# Danyboard_M0.net
KiCad netlist of a schematic drawn in EAGLE
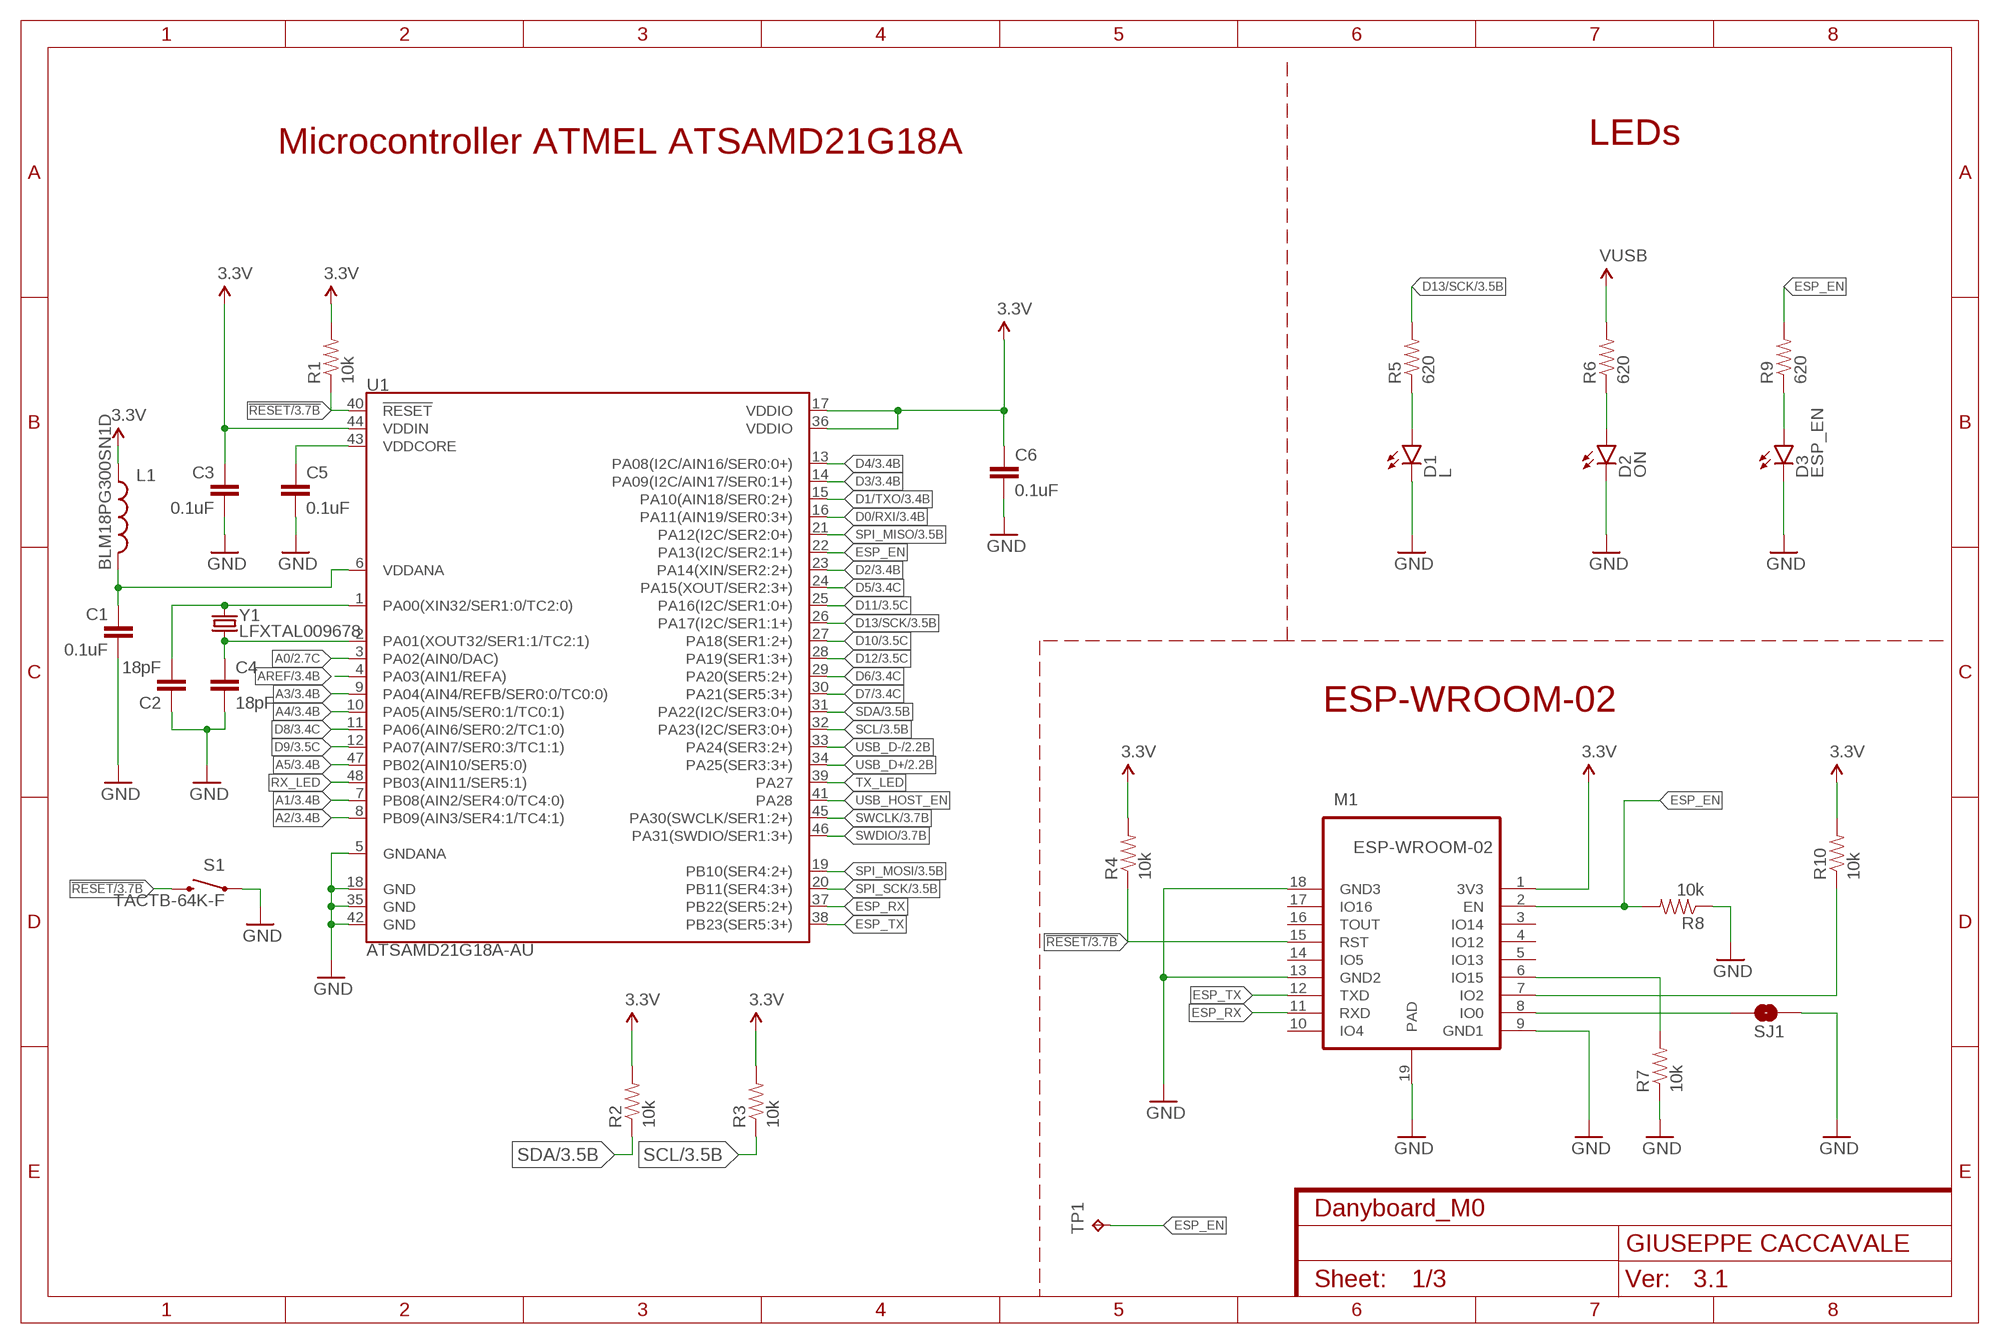
[diagram p0: schematic, sheet 1]
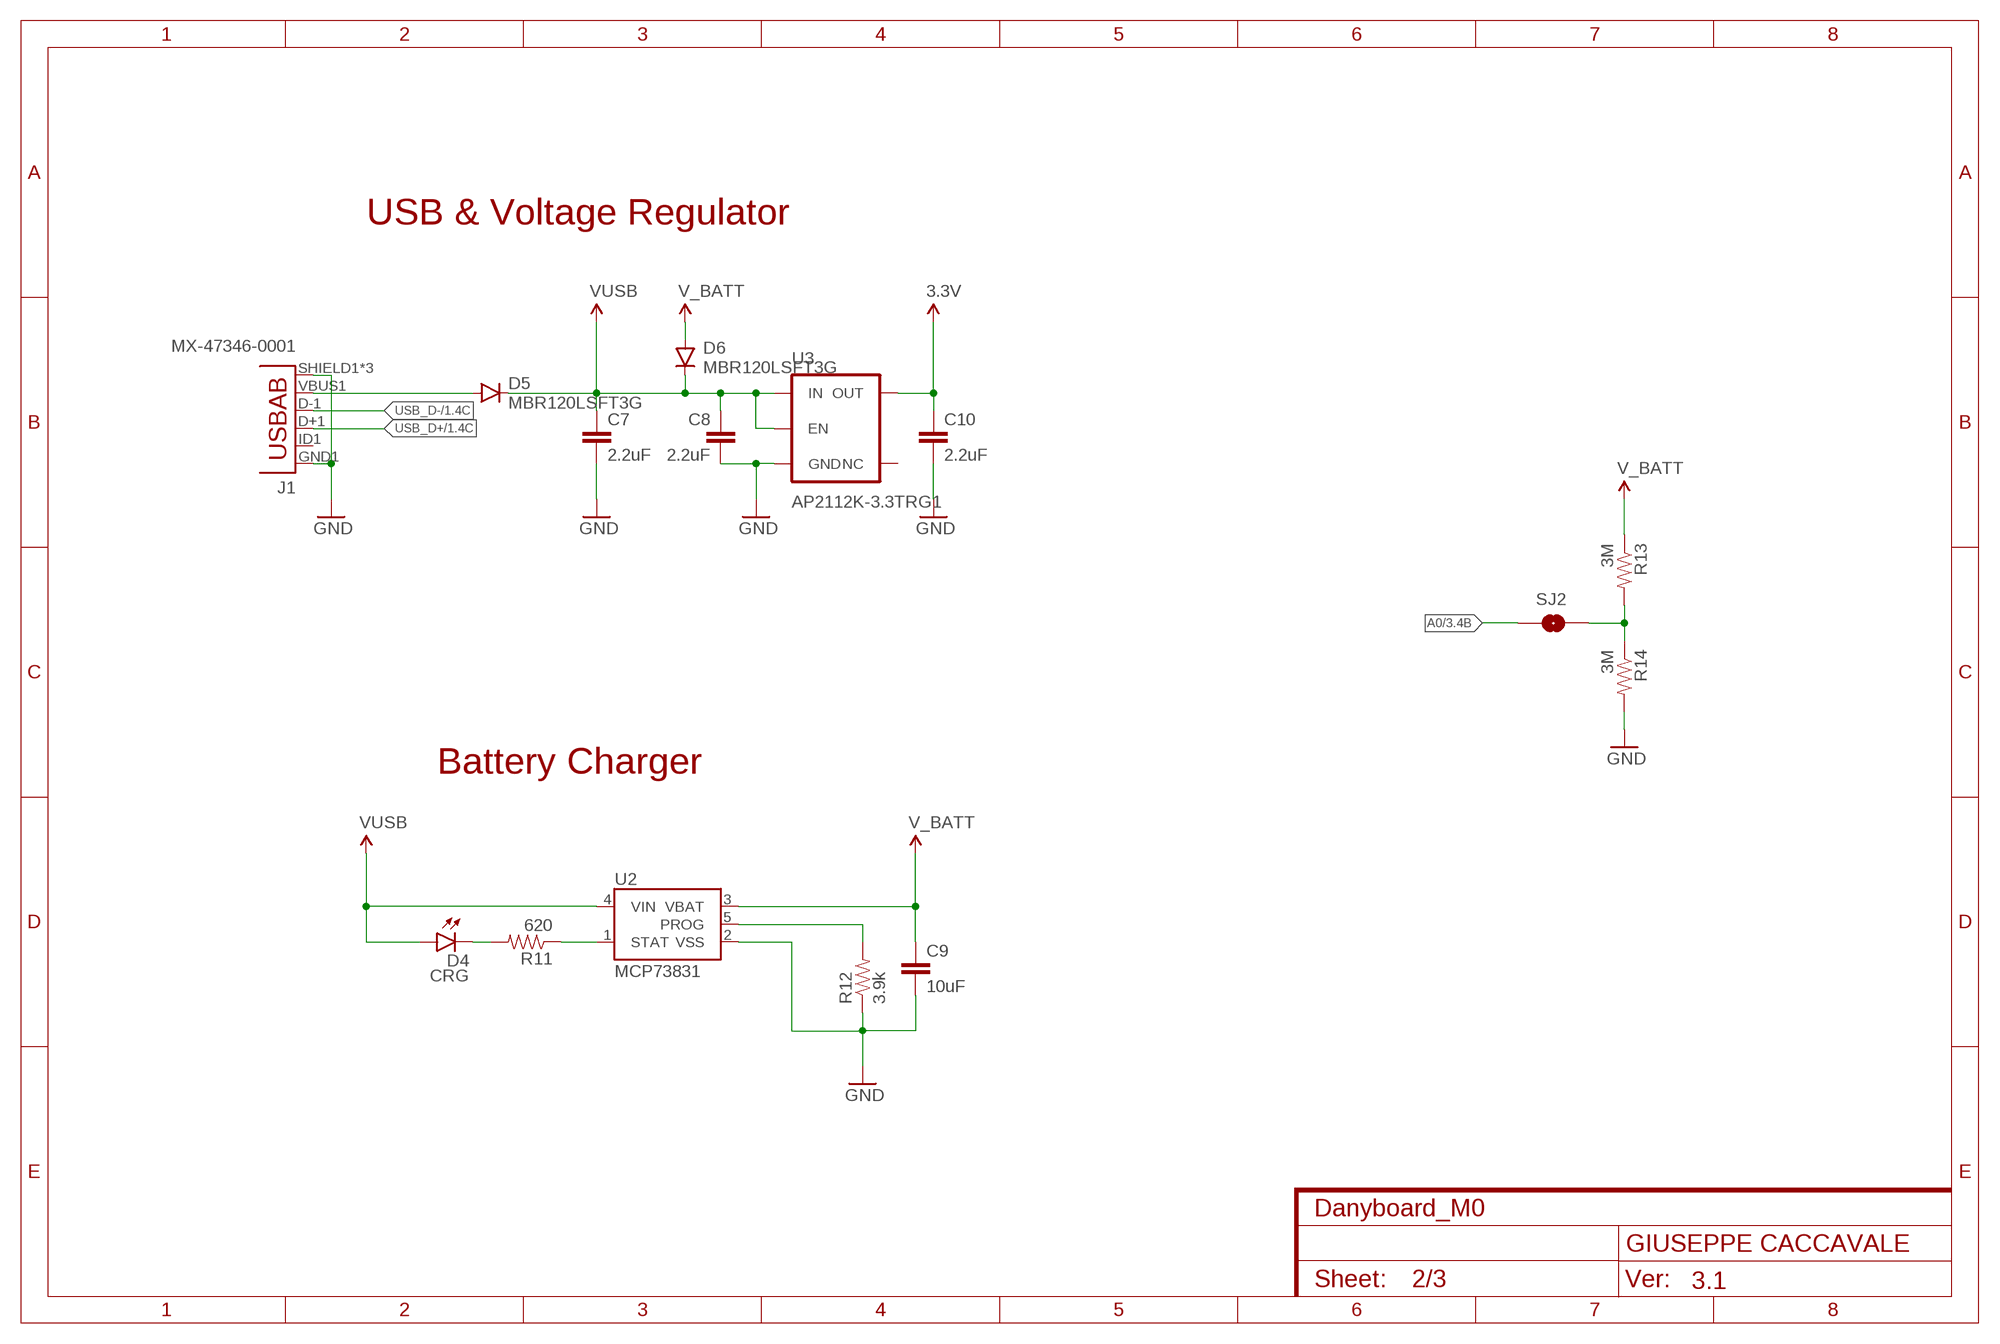
[diagram p1: schematic, sheet 2]
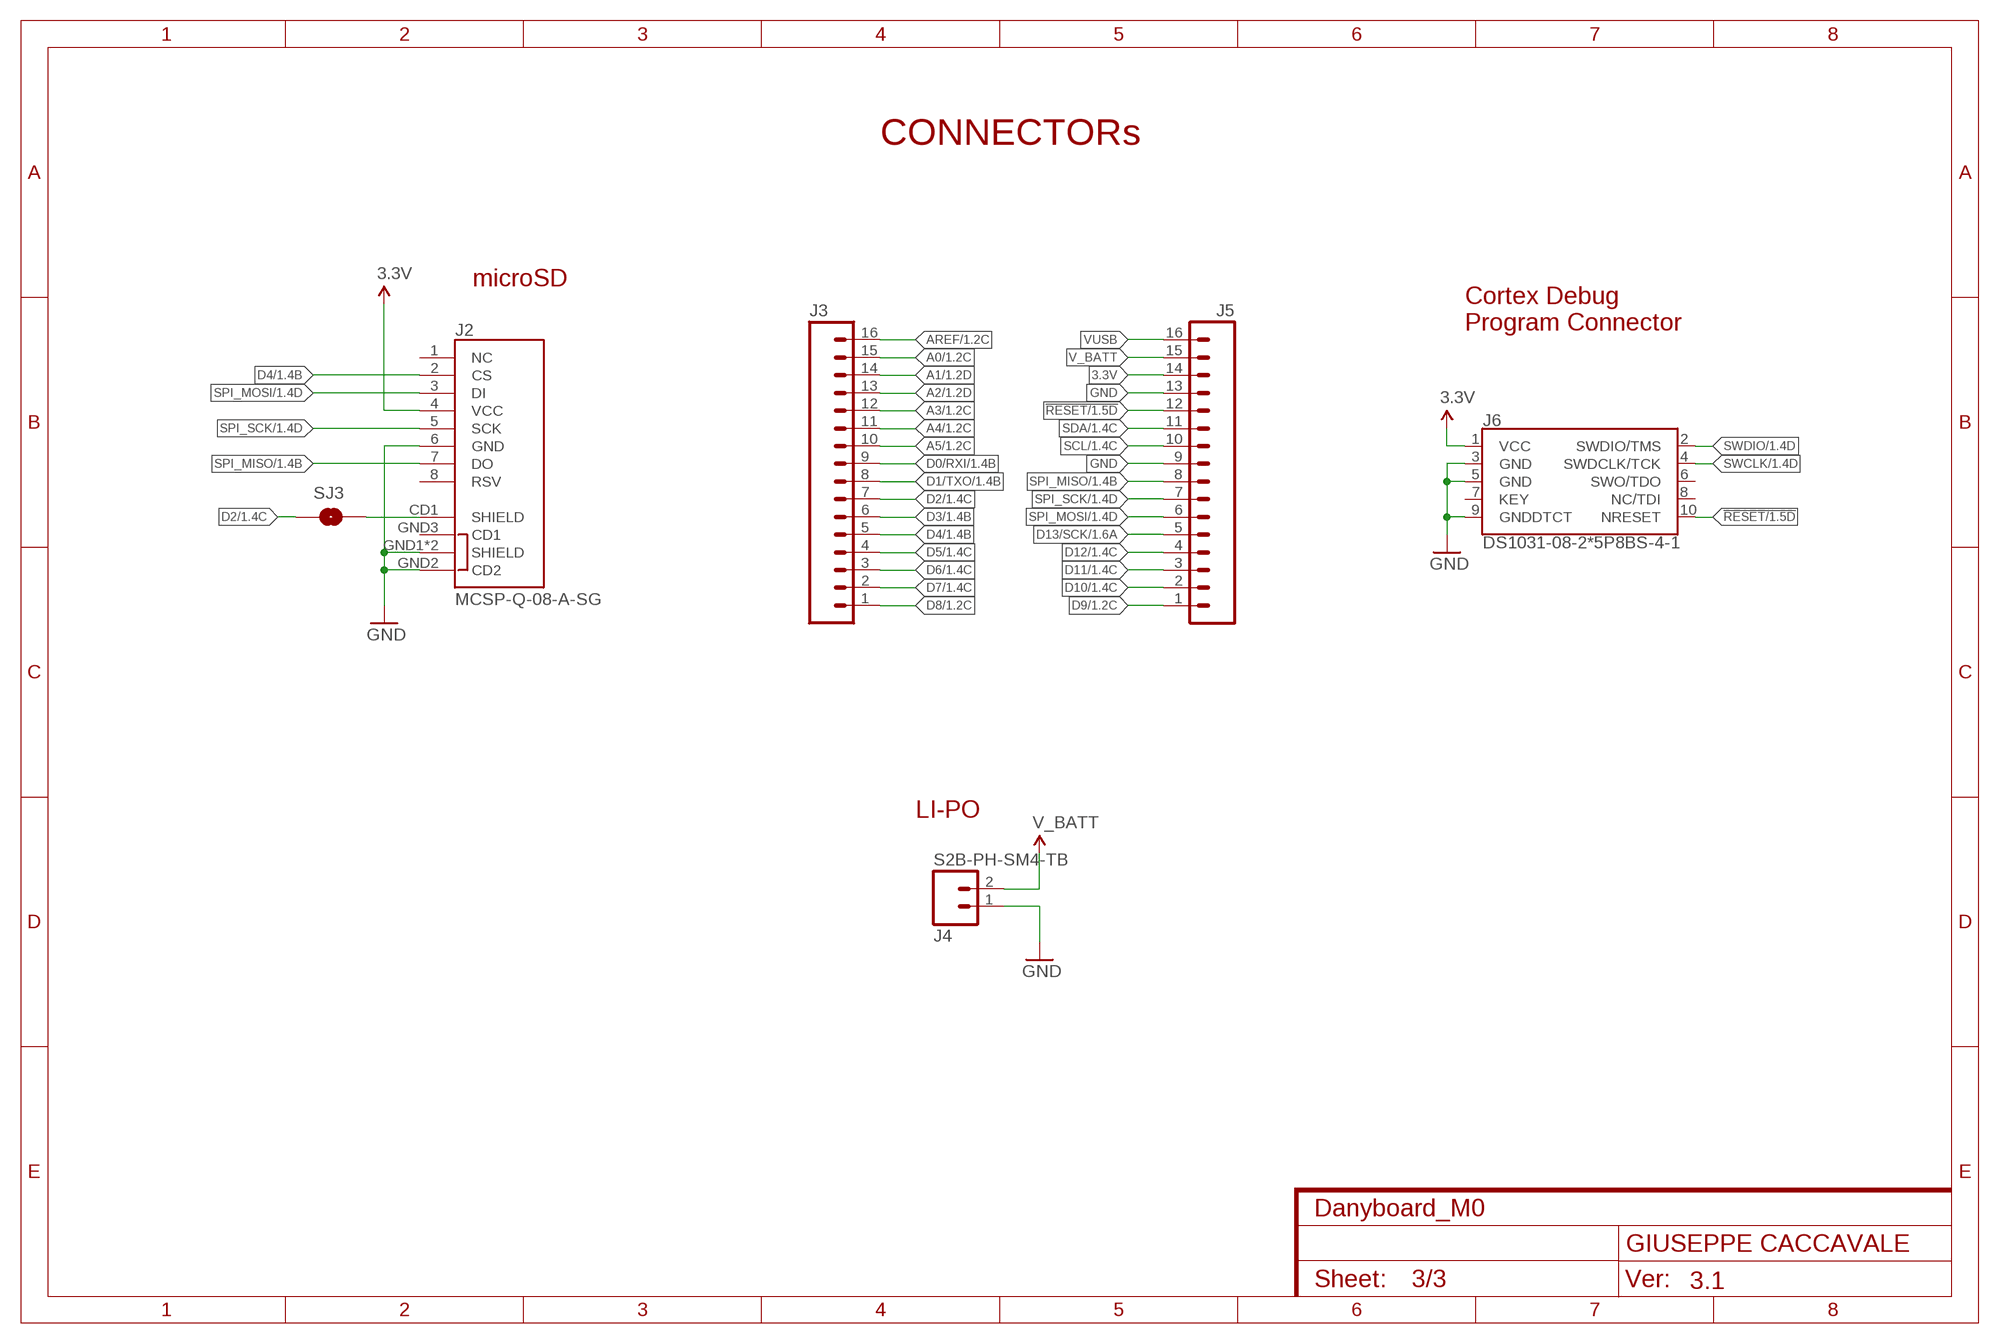
[diagram p2: schematic, sheet 3]

(export (version "E")
  (design (tool "Eeschema 10.0.6"))
  (components
    (comp (ref "C7")
      (value "2.2uF")
      (footprint "eagle-import:0603-CAP_NOSILK")
      (libsource (lib "eagle-import") (part "CAP0603-CAP_NS"))
    )
    (comp (ref "C8")
      (value "2.2uF")
      (footprint "eagle-import:0603-CAP_NOSILK")
      (libsource (lib "eagle-import") (part "CAP0603-CAP_NS"))
    )
    (comp (ref "C9")
      (value "10uF")
      (footprint "eagle-import:0603-CAP_NOSILK")
      (libsource (lib "eagle-import") (part "CAP0603-CAP_NS"))
    )
    (comp (ref "C10")
      (value "2.2uF")
      (footprint "eagle-import:0603-CAP_NOSILK")
      (libsource (lib "eagle-import") (part "CAP0603-CAP_NS"))
    )
    (comp (ref "D4")
      (value "CRG")
      (footprint "eagle-import:LED-0603")
      (libsource (lib "eagle-import") (part "LED0603"))
    )
    (comp (ref "D5")
      (value "MBR120LSFT3G")
      (footprint "eagle-import:SOD-123_NOSILK")
      (libsource (lib "eagle-import") (part "DIODESOD123_NS"))
    )
    (comp (ref "D6")
      (value "MBR120LSFT3G")
      (footprint "eagle-import:SOD-123_NOSILK")
      (libsource (lib "eagle-import") (part "DIODESOD123_NS"))
    )
    (comp (ref "J1")
      (value "MX-47346-0001")
      (footprint "eagle-import:USB-AB-MICRO-SMD_V03")
      (libsource (lib "eagle-import") (part "USB-ABCONN-11794"))
    )
    (comp (ref "R11")
      (value "620")
      (footprint "eagle-import:0603-RES_NOSILK")
      (libsource (lib "eagle-import") (part "RESISTOR0603-NS"))
    )
    (comp (ref "R12")
      (value "3.9k")
      (footprint "eagle-import:0603-RES_NOSILK")
      (libsource (lib "eagle-import") (part "RESISTOR0603-NS"))
    )
    (comp (ref "R13")
      (value "3M")
      (footprint "eagle-import:0603-RES_NOSILK")
      (libsource (lib "eagle-import") (part "RESISTOR0603-NS"))
    )
    (comp (ref "R14")
      (value "3M")
      (footprint "eagle-import:0603-RES_NOSILK")
      (libsource (lib "eagle-import") (part "RESISTOR0603-NS"))
    )
    (comp (ref "SJ2")
      (value "SOLDERJUMPERNO")
      (footprint "eagle-import:SJ_2S-NO")
      (libsource (lib "eagle-import") (part "SOLDERJUMPERNO"))
    )
    (comp (ref "U2")
      (value "MCP73831")
      (footprint "eagle-import:SOT23-5")
      (libsource (lib "eagle-import") (part "MCP73831"))
    )
    (comp (ref "U3")
      (value "AP2112K-3.3TRG1")
      (footprint "eagle-import:SOT23-5")
      (libsource (lib "eagle-import") (part "V_REG_AP2112K-3.3V"))
    )
    (comp (ref "C1")
      (value "0.1uF")
      (footprint "eagle-import:0603-CAP_NOSILK")
      (libsource (lib "eagle-import") (part "CAP0603-CAP_NS"))
    )
    (comp (ref "C2")
      (value "18pF")
      (footprint "eagle-import:0603-CAP_NOSILK")
      (libsource (lib "eagle-import") (part "CAP0603-CAP_NS"))
    )
    (comp (ref "C3")
      (value "0.1uF")
      (footprint "eagle-import:0603-CAP_NOSILK")
      (libsource (lib "eagle-import") (part "CAP0603-CAP_NS"))
    )
    (comp (ref "C4")
      (value "18pF")
      (footprint "eagle-import:0603-CAP_NOSILK")
      (libsource (lib "eagle-import") (part "CAP0603-CAP_NS"))
    )
    (comp (ref "C5")
      (value "0.1uF")
      (footprint "eagle-import:0603-CAP_NOSILK")
      (libsource (lib "eagle-import") (part "CAP0603-CAP_NS"))
    )
    (comp (ref "C6")
      (value "0.1uF")
      (footprint "eagle-import:0603-CAP_NOSILK")
      (libsource (lib "eagle-import") (part "CAP0603-CAP_NS"))
    )
    (comp (ref "D1")
      (value "L")
      (footprint "eagle-import:LED-0603")
      (libsource (lib "eagle-import") (part "LED-BLUE0603"))
    )
    (comp (ref "D2")
      (value "ON")
      (footprint "eagle-import:LED-0603")
      (libsource (lib "eagle-import") (part "LED-BLUE0603"))
    )
    (comp (ref "D3")
      (value "ESP_EN")
      (footprint "eagle-import:LED-0603")
      (libsource (lib "eagle-import") (part "LED-BLUE0603"))
    )
    (comp (ref "L1")
      (value "BLM18PG300SN1D")
      (footprint "eagle-import:0603_NOSILK")
      (libsource (lib "eagle-import") (part "INDUCTOR0603_NS"))
    )
    (comp (ref "M1")
      (value "ESP-WROOM-02")
      (footprint "eagle-import:ESP-WROOM-02_NOSILK")
      (libsource (lib "eagle-import") (part "ESP-WROOM-02-NS"))
    )
    (comp (ref "R1")
      (value "10k")
      (footprint "eagle-import:0603-RES_NOSILK")
      (libsource (lib "eagle-import") (part "RESISTOR0603-NS"))
    )
    (comp (ref "R2")
      (value "10k")
      (footprint "eagle-import:0603-RES_NOSILK")
      (libsource (lib "eagle-import") (part "RESISTOR0603-NS"))
    )
    (comp (ref "R3")
      (value "10k")
      (footprint "eagle-import:0603-RES_NOSILK")
      (libsource (lib "eagle-import") (part "RESISTOR0603-NS"))
    )
    (comp (ref "R4")
      (value "10k")
      (footprint "eagle-import:0603-RES_NOSILK")
      (libsource (lib "eagle-import") (part "RESISTOR0603-NS"))
    )
    (comp (ref "R5")
      (value "620")
      (footprint "eagle-import:0603-RES_NOSILK")
      (libsource (lib "eagle-import") (part "RESISTOR0603-NS"))
    )
    (comp (ref "R6")
      (value "620")
      (footprint "eagle-import:0603-RES_NOSILK")
      (libsource (lib "eagle-import") (part "RESISTOR0603-NS"))
    )
    (comp (ref "R7")
      (value "10k")
      (footprint "eagle-import:0603-RES_NOSILK")
      (libsource (lib "eagle-import") (part "RESISTOR0603-NS"))
    )
    (comp (ref "R8")
      (value "10k")
      (footprint "eagle-import:0603-RES_NOSILK")
      (libsource (lib "eagle-import") (part "RESISTOR0603-NS"))
    )
    (comp (ref "R9")
      (value "620")
      (footprint "eagle-import:0603-RES_NOSILK")
      (libsource (lib "eagle-import") (part "RESISTOR0603-NS"))
    )
    (comp (ref "R10")
      (value "10k")
      (footprint "eagle-import:0603-RES_NOSILK")
      (libsource (lib "eagle-import") (part "RESISTOR0603-NS"))
    )
    (comp (ref "S1")
      (value "TACTB-64K-F")
      (footprint "eagle-import:TACTILE-SWITCH-SMD_NOSILK")
      (libsource (lib "eagle-import") (part "SWITCH-MOMENTARY-2SMD-NS"))
    )
    (comp (ref "SJ1")
      (value "SOLDERJUMPERNO")
      (footprint "eagle-import:SJ_2S-NO")
      (libsource (lib "eagle-import") (part "SOLDERJUMPERNO"))
    )
    (comp (ref "TP1")
      (value "ESP8266")
      (footprint "eagle-import:B1,27")
      (libsource (lib "eagle-import") (part "TPB1,27"))
    )
    (comp (ref "U1")
      (value "ATSAMD21G18A-AU")
      (footprint "eagle-import:TQFP-48_NOSILK")
      (libsource (lib "eagle-import") (part "ATSAMD21G-A2"))
    )
    (comp (ref "Y1")
      (value "LFXTAL009678")
      (footprint "eagle-import:CRYSTAL-SMD-3.2X1.5MM_NOSILK")
      (libsource (lib "eagle-import") (part "CRYSTAL3.2X1.5MM_NS"))
    )
    (comp (ref "J2")
      (value "MCSP-Q-08-A-SG")
      (footprint "eagle-import:MCSP-Q-08-A-SG-T_NOSILK")
      (libsource (lib "eagle-import") (part "USD-SOCKET-NS"))
    )
    (comp (ref "J3")
      (value "M161X16_NO_SILK")
      (footprint "eagle-import:1X16_NO_SILK")
      (libsource (lib "eagle-import") (part "M161X16_NO_SILK"))
    )
    (comp (ref "J4")
      (value "S2B-PH-SM4-TB")
      (footprint "eagle-import:JST-2-SMD_NOSILK")
      (libsource (lib "eagle-import") (part "M02-JST-2MM-SMT_NS"))
    )
    (comp (ref "J5")
      (value "M161X16_NO_SILK")
      (footprint "eagle-import:1X16_NO_SILK")
      (libsource (lib "eagle-import") (part "M161X16_NO_SILK"))
    )
    (comp (ref "J6")
      (value "DS1031-08-2*5P8BS-4-1")
      (footprint "eagle-import:SAMTECH_FTSH-105-01_NOSILK")
      (libsource (lib "eagle-import") (part "CORTEX_DEBUGSMD2"))
    )
    (comp (ref "SJ3")
      (value "SOLDERJUMPERNO")
      (footprint "eagle-import:SJ_2S-NO")
      (libsource (lib "eagle-import") (part "SOLDERJUMPERNO"))
    )
  )
  (nets
    (net (code "1") (name "3.3V") (class "Default")
      (node (ref "C10") (pin "1") (pinfunction "1_1") (pintype "passive"))
      (node (ref "C3") (pin "1") (pinfunction "1_1") (pintype "passive"))
      (node (ref "C6") (pin "1") (pinfunction "1_1") (pintype "passive"))
      (node (ref "J2") (pin "4") (pinfunction "VCC_4") (pintype "bidirectional"))
      (node (ref "J5") (pin "14") (pinfunction "14_14") (pintype "passive"))
      (node (ref "J6") (pin "1") (pinfunction "VCC_1") (pintype "bidirectional"))
      (node (ref "L1") (pin "1") (pinfunction "1_1") (pintype "passive"))
      (node (ref "M1") (pin "1") (pinfunction "3V3_1") (pintype "power_in"))
      (node (ref "R1") (pin "2") (pinfunction "2_2") (pintype "passive"))
      (node (ref "R10") (pin "2") (pinfunction "2_2") (pintype "passive"))
      (node (ref "R2") (pin "2") (pinfunction "2_2") (pintype "passive"))
      (node (ref "R3") (pin "2") (pinfunction "2_2") (pintype "passive"))
      (node (ref "R4") (pin "2") (pinfunction "2_2") (pintype "passive"))
      (node (ref "U1") (pin "17") (pinfunction "VDDIO_17") (pintype "bidirectional"))
      (node (ref "U1") (pin "36") (pinfunction "VDDIO_36") (pintype "bidirectional"))
      (node (ref "U1") (pin "44") (pinfunction "VDDIN_44") (pintype "bidirectional"))
      (node (ref "U3") (pin "5") (pinfunction "OUT_5") (pintype "passive"))
    )
    (net (code "2") (name "A0") (class "Default")
      (node (ref "J3") (pin "15") (pinfunction "15_15") (pintype "passive"))
      (node (ref "SJ2") (pin "1") (pinfunction "1_1") (pintype "passive"))
      (node (ref "U1") (pin "3") (pinfunction "PA02(AIN0/DAC)_3") (pintype "bidirectional"))
    )
    (net (code "3") (name "A1") (class "Default")
      (node (ref "J3") (pin "14") (pinfunction "14_14") (pintype "passive"))
      (node (ref "U1") (pin "7") (pinfunction "PB08(AIN2/SER4:0/TC4:0)_7") (pintype "bidirectional"))
    )
    (net (code "4") (name "A2") (class "Default")
      (node (ref "J3") (pin "13") (pinfunction "13_13") (pintype "passive"))
      (node (ref "U1") (pin "8") (pinfunction "PB09(AIN3/SER4:1/TC4:1)_8") (pintype "bidirectional"))
    )
    (net (code "5") (name "A3") (class "Default")
      (node (ref "J3") (pin "12") (pinfunction "12_12") (pintype "passive"))
      (node (ref "U1") (pin "9") (pinfunction "PA04(AIN4/REFB/SER0:0/TC0:0)_9") (pintype "bidirectional"))
    )
    (net (code "6") (name "A4") (class "Default")
      (node (ref "J3") (pin "11") (pinfunction "11_11") (pintype "passive"))
      (node (ref "U1") (pin "10") (pinfunction "PA05(AIN5/SER0:1/TC0:1)_10") (pintype "bidirectional"))
    )
    (net (code "7") (name "A5") (class "Default")
      (node (ref "J3") (pin "10") (pinfunction "10_10") (pintype "passive"))
      (node (ref "U1") (pin "47") (pinfunction "PB02(AIN10/SER5:0)_47") (pintype "bidirectional"))
    )
    (net (code "8") (name "AREF") (class "Default")
      (node (ref "J3") (pin "16") (pinfunction "16_16") (pintype "passive"))
      (node (ref "U1") (pin "4") (pinfunction "PA03(AIN1/REFA)_4") (pintype "bidirectional"))
    )
    (net (code "9") (name "D0{slash}RXI") (class "Default")
      (node (ref "J3") (pin "9") (pinfunction "9_9") (pintype "passive"))
      (node (ref "U1") (pin "16") (pinfunction "PA11(AIN19/SER0:3+)_16") (pintype "bidirectional"))
    )
    (net (code "10") (name "D1{slash}TXO") (class "Default")
      (node (ref "J3") (pin "8") (pinfunction "8_8") (pintype "passive"))
      (node (ref "U1") (pin "15") (pinfunction "PA10(AIN18/SER0:2+)_15") (pintype "bidirectional"))
    )
    (net (code "11") (name "D2") (class "Default")
      (node (ref "J3") (pin "7") (pinfunction "7_7") (pintype "passive"))
      (node (ref "SJ3") (pin "1") (pinfunction "1_1") (pintype "passive"))
      (node (ref "U1") (pin "23") (pinfunction "PA14(XIN/SER2:2+)_23") (pintype "bidirectional"))
    )
    (net (code "12") (name "D3") (class "Default")
      (node (ref "J3") (pin "6") (pinfunction "6_6") (pintype "passive"))
      (node (ref "U1") (pin "14") (pinfunction "PA09(I2C/AIN17/SER0:1+)_14") (pintype "bidirectional"))
    )
    (net (code "13") (name "D4") (class "Default")
      (node (ref "J2") (pin "2") (pinfunction "CS_2") (pintype "bidirectional"))
      (node (ref "J3") (pin "5") (pinfunction "5_5") (pintype "passive"))
      (node (ref "U1") (pin "13") (pinfunction "PA08(I2C/AIN16/SER0:0+)_13") (pintype "bidirectional"))
    )
    (net (code "14") (name "D5") (class "Default")
      (node (ref "J3") (pin "4") (pinfunction "4_4") (pintype "passive"))
      (node (ref "U1") (pin "24") (pinfunction "PA15(XOUT/SER2:3+)_24") (pintype "bidirectional"))
    )
    (net (code "15") (name "D6") (class "Default")
      (node (ref "J3") (pin "3") (pinfunction "3_3") (pintype "passive"))
      (node (ref "U1") (pin "29") (pinfunction "PA20(SER5:2+)_29") (pintype "bidirectional"))
    )
    (net (code "16") (name "D7") (class "Default")
      (node (ref "J3") (pin "2") (pinfunction "2_2") (pintype "passive"))
      (node (ref "U1") (pin "30") (pinfunction "PA21(SER5:3+)_30") (pintype "bidirectional"))
    )
    (net (code "17") (name "D8") (class "Default")
      (node (ref "J3") (pin "1") (pinfunction "1_1") (pintype "passive"))
      (node (ref "U1") (pin "11") (pinfunction "PA06(AIN6/SER0:2/TC1:0)_11") (pintype "bidirectional"))
    )
    (net (code "18") (name "D9") (class "Default")
      (node (ref "J5") (pin "1") (pinfunction "1_1") (pintype "passive"))
      (node (ref "U1") (pin "12") (pinfunction "PA07(AIN7/SER0:3/TC1:1)_12") (pintype "bidirectional"))
    )
    (net (code "19") (name "D10") (class "Default")
      (node (ref "J5") (pin "2") (pinfunction "2_2") (pintype "passive"))
      (node (ref "U1") (pin "27") (pinfunction "PA18(SER1:2+)_27") (pintype "bidirectional"))
    )
    (net (code "20") (name "D11") (class "Default")
      (node (ref "J5") (pin "3") (pinfunction "3_3") (pintype "passive"))
      (node (ref "U1") (pin "25") (pinfunction "PA16(I2C/SER1:0+)_25") (pintype "bidirectional"))
    )
    (net (code "21") (name "D12") (class "Default")
      (node (ref "J5") (pin "4") (pinfunction "4_4") (pintype "passive"))
      (node (ref "U1") (pin "28") (pinfunction "PA19(SER1:3+)_28") (pintype "bidirectional"))
    )
    (net (code "22") (name "D13{slash}SCK") (class "Default")
      (node (ref "J5") (pin "5") (pinfunction "5_5") (pintype "passive"))
      (node (ref "R5") (pin "2") (pinfunction "2_2") (pintype "passive"))
      (node (ref "U1") (pin "26") (pinfunction "PA17(I2C/SER1:1+)_26") (pintype "bidirectional"))
    )
    (net (code "23") (name "ESP_EN") (class "Default")
      (node (ref "M1") (pin "2") (pinfunction "EN_2") (pintype "bidirectional"))
      (node (ref "R8") (pin "2") (pinfunction "2_2") (pintype "passive"))
      (node (ref "R9") (pin "2") (pinfunction "2_2") (pintype "passive"))
      (node (ref "TP1") (pin "TP") (pinfunction "TP_TP") (pintype "input"))
      (node (ref "U1") (pin "22") (pinfunction "PA13(I2C/SER2:1+)_22") (pintype "bidirectional"))
    )
    (net (code "24") (name "ESP_RX") (class "Default")
      (node (ref "M1") (pin "11") (pinfunction "RXD_11") (pintype "bidirectional"))
      (node (ref "U1") (pin "37") (pinfunction "PB22(SER5:2+)_37") (pintype "bidirectional"))
    )
    (net (code "25") (name "ESP_TX") (class "Default")
      (node (ref "M1") (pin "12") (pinfunction "TXD_12") (pintype "bidirectional"))
      (node (ref "U1") (pin "38") (pinfunction "PB23(SER5:3+)_38") (pintype "bidirectional"))
    )
    (net (code "26") (name "GND") (class "Default")
      (node (ref "C1") (pin "2") (pinfunction "2_2") (pintype "passive"))
      (node (ref "C10") (pin "2") (pinfunction "2_2") (pintype "passive"))
      (node (ref "C2") (pin "1") (pinfunction "1_1") (pintype "passive"))
      (node (ref "C3") (pin "2") (pinfunction "2_2") (pintype "passive"))
      (node (ref "C4") (pin "2") (pinfunction "2_2") (pintype "passive"))
      (node (ref "C5") (pin "2") (pinfunction "2_2") (pintype "passive"))
      (node (ref "C6") (pin "2") (pinfunction "2_2") (pintype "passive"))
      (node (ref "C7") (pin "2") (pinfunction "2_2") (pintype "passive"))
      (node (ref "C8") (pin "2") (pinfunction "2_2") (pintype "passive"))
      (node (ref "C9") (pin "2") (pinfunction "2_2") (pintype "passive"))
      (node (ref "D1") (pin "C") (pinfunction "C_C") (pintype "passive"))
      (node (ref "D2") (pin "C") (pinfunction "C_C") (pintype "passive"))
      (node (ref "D3") (pin "C") (pinfunction "C_C") (pintype "passive"))
      (node (ref "J1") (pin "GND1") (pinfunction "GND_GND1") (pintype "bidirectional"))
      (node (ref "J1") (pin "SHIELD1") (pinfunction "SHIELD_SHIELD1") (pintype "bidirectional"))
      (node (ref "J1") (pin "SHIELD2") (pinfunction "SHIELD_SHIELD2") (pintype "bidirectional"))
      (node (ref "J1") (pin "SHIELD3") (pinfunction "SHIELD_SHIELD3") (pintype "bidirectional"))
      (node (ref "J2") (pin "6") (pinfunction "GND_6") (pintype "bidirectional"))
      (node (ref "J2") (pin "GND1") (pinfunction "SHIELD_GND1") (pintype "bidirectional"))
      (node (ref "J2") (pin "GND2") (pinfunction "CD2_GND2") (pintype "bidirectional"))
      (node (ref "J2") (pin "GND4") (pinfunction "SHIELD_GND4") (pintype "bidirectional"))
      (node (ref "J4") (pin "1") (pinfunction "2_1") (pintype "passive"))
      (node (ref "J5") (pin "13") (pinfunction "13_13") (pintype "passive"))
      (node (ref "J5") (pin "9") (pinfunction "9_9") (pintype "passive"))
      (node (ref "J6") (pin "3") (pinfunction "GND_3") (pintype "bidirectional"))
      (node (ref "J6") (pin "5") (pinfunction "GND_5") (pintype "bidirectional"))
      (node (ref "J6") (pin "9") (pinfunction "GNDDTCT_9") (pintype "bidirectional"))
      (node (ref "M1") (pin "13") (pinfunction "GND2_13") (pintype "power_in"))
      (node (ref "M1") (pin "18") (pinfunction "GND3_18") (pintype "power_in"))
      (node (ref "M1") (pin "19") (pinfunction "PAD_19") (pintype "bidirectional"))
      (node (ref "M1") (pin "9") (pinfunction "GND1_9") (pintype "power_in"))
      (node (ref "R12") (pin "1") (pinfunction "1_1") (pintype "passive"))
      (node (ref "R14") (pin "2") (pinfunction "2_2") (pintype "passive"))
      (node (ref "R7") (pin "1") (pinfunction "1_1") (pintype "passive"))
      (node (ref "R8") (pin "1") (pinfunction "1_1") (pintype "passive"))
      (node (ref "S1") (pin "1") (pinfunction "1_1") (pintype "passive"))
      (node (ref "SJ1") (pin "2") (pinfunction "2_2") (pintype "passive"))
      (node (ref "U1") (pin "18") (pinfunction "GND_18") (pintype "bidirectional"))
      (node (ref "U1") (pin "35") (pinfunction "GND_35") (pintype "bidirectional"))
      (node (ref "U1") (pin "42") (pinfunction "GND_42") (pintype "bidirectional"))
      (node (ref "U1") (pin "5") (pinfunction "GNDANA_5") (pintype "bidirectional"))
      (node (ref "U2") (pin "2") (pinfunction "VSS_2") (pintype "power_in"))
      (node (ref "U3") (pin "2") (pinfunction "GND_2") (pintype "input"))
    )
    (net (code "27") (name "Net-(D1-PadA)") (class "Default")
      (node (ref "D1") (pin "A") (pinfunction "A_A") (pintype "passive"))
      (node (ref "R5") (pin "1") (pinfunction "1_1") (pintype "passive"))
    )
    (net (code "28") (name "Net-(D2-PadA)") (class "Default")
      (node (ref "D2") (pin "A") (pinfunction "A_A") (pintype "passive"))
      (node (ref "R6") (pin "1") (pinfunction "1_1") (pintype "passive"))
    )
    (net (code "29") (name "Net-(D3-PadA)") (class "Default")
      (node (ref "D3") (pin "A") (pinfunction "A_A") (pintype "passive"))
      (node (ref "R9") (pin "1") (pinfunction "1_1") (pintype "passive"))
    )
    (net (code "30") (name "Net-(D4-PadC)") (class "Default")
      (node (ref "D4") (pin "C") (pinfunction "C_C") (pintype "passive"))
      (node (ref "R11") (pin "2") (pinfunction "2_2") (pintype "passive"))
    )
    (net (code "31") (name "Net-(J1-VBUS)") (class "Default")
      (node (ref "D5") (pin "A") (pinfunction "A_A") (pintype "passive"))
      (node (ref "J1") (pin "VBUS1") (pinfunction "VBUS_VBUS1") (pintype "bidirectional"))
    )
    (net (code "32") (name "Net-(J2-SHIELD-PadCD1)") (class "Default")
      (node (ref "J2") (pin "CD1") (pinfunction "SHIELD_CD1") (pintype "bidirectional"))
      (node (ref "SJ3") (pin "2") (pinfunction "2_2") (pintype "passive"))
    )
    (net (code "33") (name "Net-(M1-IO0)") (class "Default")
      (node (ref "M1") (pin "8") (pinfunction "IO0_8") (pintype "bidirectional"))
      (node (ref "SJ1") (pin "1") (pinfunction "1_1") (pintype "passive"))
    )
    (net (code "34") (name "Net-(M1-IO2)") (class "Default")
      (node (ref "M1") (pin "7") (pinfunction "IO2_7") (pintype "bidirectional"))
      (node (ref "R10") (pin "1") (pinfunction "1_1") (pintype "passive"))
    )
    (net (code "35") (name "Net-(M1-IO15)") (class "Default")
      (node (ref "M1") (pin "6") (pinfunction "IO15_6") (pintype "bidirectional"))
      (node (ref "R7") (pin "2") (pinfunction "2_2") (pintype "passive"))
    )
    (net (code "36") (name "Net-(R13-Pad2)") (class "Default")
      (node (ref "R13") (pin "2") (pinfunction "2_2") (pintype "passive"))
      (node (ref "R14") (pin "1") (pinfunction "1_1") (pintype "passive"))
      (node (ref "SJ2") (pin "2") (pinfunction "2_2") (pintype "passive"))
    )
    (net (code "37") (name "Net-(U1-PA00(XIN32{slash}SER1:0{slash}TC2:0))") (class "Default")
      (node (ref "C2") (pin "2") (pinfunction "2_2") (pintype "passive"))
      (node (ref "U1") (pin "1") (pinfunction "PA00(XIN32/SER1:0/TC2:0)_1") (pintype "bidirectional"))
      (node (ref "Y1") (pin "P$2") (pinfunction "2_P$2") (pintype "passive"))
    )
    (net (code "38") (name "Net-(U1-PA01(XOUT32{slash}SER1:1{slash}TC2:1))") (class "Default")
      (node (ref "C4") (pin "1") (pinfunction "1_1") (pintype "passive"))
      (node (ref "U1") (pin "2") (pinfunction "PA01(XOUT32/SER1:1/TC2:1)_2") (pintype "bidirectional"))
      (node (ref "Y1") (pin "P$1") (pinfunction "1_P$1") (pintype "passive"))
    )
    (net (code "39") (name "Net-(U1-VDDANA)") (class "Default")
      (node (ref "C1") (pin "1") (pinfunction "1_1") (pintype "passive"))
      (node (ref "L1") (pin "2") (pinfunction "2_2") (pintype "passive"))
      (node (ref "U1") (pin "6") (pinfunction "VDDANA_6") (pintype "bidirectional"))
    )
    (net (code "40") (name "Net-(U1-VDDCORE)") (class "Default")
      (node (ref "C5") (pin "1") (pinfunction "1_1") (pintype "passive"))
      (node (ref "U1") (pin "43") (pinfunction "VDDCORE_43") (pintype "bidirectional"))
    )
    (net (code "41") (name "Net-(U2-PROG)") (class "Default")
      (node (ref "R12") (pin "2") (pinfunction "2_2") (pintype "passive"))
      (node (ref "U2") (pin "5") (pinfunction "PROG_5") (pintype "input"))
    )
    (net (code "42") (name "Net-(U2-STAT)") (class "Default")
      (node (ref "R11") (pin "1") (pinfunction "1_1") (pintype "passive"))
      (node (ref "U2") (pin "1") (pinfunction "STAT_1") (pintype "output"))
    )
    (net (code "43") (name "RX_LED") (class "Default")
      (node (ref "U1") (pin "48") (pinfunction "PB03(AIN11/SER5:1)_48") (pintype "bidirectional"))
    )
    (net (code "44") (name "SCL") (class "Default")
      (node (ref "J5") (pin "10") (pinfunction "10_10") (pintype "passive"))
      (node (ref "R3") (pin "1") (pinfunction "1_1") (pintype "passive"))
      (node (ref "U1") (pin "32") (pinfunction "PA23(I2C/SER3:0+)_32") (pintype "bidirectional"))
    )
    (net (code "45") (name "SDA") (class "Default")
      (node (ref "J5") (pin "11") (pinfunction "11_11") (pintype "passive"))
      (node (ref "R2") (pin "1") (pinfunction "1_1") (pintype "passive"))
      (node (ref "U1") (pin "31") (pinfunction "PA22(I2C/SER3:0+)_31") (pintype "bidirectional"))
    )
    (net (code "46") (name "SPI_MISO") (class "Default")
      (node (ref "J2") (pin "7") (pinfunction "DO_7") (pintype "bidirectional"))
      (node (ref "J5") (pin "8") (pinfunction "8_8") (pintype "passive"))
      (node (ref "U1") (pin "21") (pinfunction "PA12(I2C/SER2:0+)_21") (pintype "bidirectional"))
    )
    (net (code "47") (name "SPI_MOSI") (class "Default")
      (node (ref "J2") (pin "3") (pinfunction "DI_3") (pintype "bidirectional"))
      (node (ref "J5") (pin "6") (pinfunction "6_6") (pintype "passive"))
      (node (ref "U1") (pin "19") (pinfunction "PB10(SER4:2+)_19") (pintype "bidirectional"))
    )
    (net (code "48") (name "SPI_SCK") (class "Default")
      (node (ref "J2") (pin "5") (pinfunction "SCK_5") (pintype "bidirectional"))
      (node (ref "J5") (pin "7") (pinfunction "7_7") (pintype "passive"))
      (node (ref "U1") (pin "20") (pinfunction "PB11(SER4:3+)_20") (pintype "bidirectional"))
    )
    (net (code "49") (name "SWCLK") (class "Default")
      (node (ref "J6") (pin "4") (pinfunction "SWDCLK/TCK_4") (pintype "bidirectional"))
      (node (ref "U1") (pin "45") (pinfunction "PA30(SWCLK/SER1:2+)_45") (pintype "bidirectional"))
    )
    (net (code "50") (name "SWDIO") (class "Default")
      (node (ref "J6") (pin "2") (pinfunction "SWDIO/TMS_2") (pintype "bidirectional"))
      (node (ref "U1") (pin "46") (pinfunction "PA31(SWDIO/SER1:3+)_46") (pintype "bidirectional"))
    )
    (net (code "51") (name "TX_LED") (class "Default")
      (node (ref "U1") (pin "39") (pinfunction "PA27_39") (pintype "bidirectional"))
    )
    (net (code "52") (name "USB_D+") (class "Default")
      (node (ref "J1") (pin "D+1") (pinfunction "D+_D+1") (pintype "bidirectional"))
      (node (ref "U1") (pin "34") (pinfunction "PA25(SER3:3+)_34") (pintype "bidirectional"))
    )
    (net (code "53") (name "USB_D-") (class "Default")
      (node (ref "J1") (pin "D-1") (pinfunction "D-_D-1") (pintype "bidirectional"))
      (node (ref "U1") (pin "33") (pinfunction "PA24(SER3:2+)_33") (pintype "bidirectional"))
    )
    (net (code "54") (name "USB_HOST_EN") (class "Default")
      (node (ref "U1") (pin "41") (pinfunction "PA28_41") (pintype "bidirectional"))
    )
    (net (code "55") (name "VUSB") (class "Default")
      (node (ref "C7") (pin "1") (pinfunction "1_1") (pintype "passive"))
      (node (ref "C8") (pin "1") (pinfunction "1_1") (pintype "passive"))
      (node (ref "D4") (pin "A") (pinfunction "A_A") (pintype "passive"))
      (node (ref "D5") (pin "C") (pinfunction "C_C") (pintype "passive"))
      (node (ref "D6") (pin "C") (pinfunction "C_C") (pintype "passive"))
      (node (ref "J5") (pin "16") (pinfunction "16_16") (pintype "passive"))
      (node (ref "R6") (pin "2") (pinfunction "2_2") (pintype "passive"))
      (node (ref "U2") (pin "4") (pinfunction "VIN_4") (pintype "power_in"))
      (node (ref "U3") (pin "1") (pinfunction "IN_1") (pintype "input"))
      (node (ref "U3") (pin "3") (pinfunction "EN_3") (pintype "input"))
    )
    (net (code "56") (name "V_BATT") (class "Default")
      (node (ref "C9") (pin "1") (pinfunction "1_1") (pintype "passive"))
      (node (ref "D6") (pin "A") (pinfunction "A_A") (pintype "passive"))
      (node (ref "J4") (pin "2") (pinfunction "1_2") (pintype "passive"))
      (node (ref "J5") (pin "15") (pinfunction "15_15") (pintype "passive"))
      (node (ref "R13") (pin "1") (pinfunction "1_1") (pintype "passive"))
      (node (ref "U2") (pin "3") (pinfunction "VBAT_3") (pintype "power_in"))
    )
    (net (code "57") (name "unconnected-(J1-USBID-PadID1)") (class "Default")
      (node (ref "J1") (pin "ID1") (pinfunction "USBID_ID1") (pintype "bidirectional"))
    )
    (net (code "58") (name "unconnected-(J2-CD1-PadGND3)") (class "Default")
      (node (ref "J2") (pin "GND3") (pinfunction "CD1_GND3") (pintype "bidirectional"))
    )
    (net (code "59") (name "unconnected-(J2-NC-Pad1)") (class "Default")
      (node (ref "J2") (pin "1") (pinfunction "NC_1") (pintype "bidirectional"))
    )
    (net (code "60") (name "unconnected-(J2-RSV-Pad8)") (class "Default")
      (node (ref "J2") (pin "8") (pinfunction "RSV_8") (pintype "bidirectional"))
    )
    (net (code "61") (name "unconnected-(J6-KEY-Pad7)") (class "Default")
      (node (ref "J6") (pin "7") (pinfunction "KEY_7") (pintype "bidirectional"))
    )
    (net (code "62") (name "unconnected-(J6-NC{slash}TDI-Pad8)") (class "Default")
      (node (ref "J6") (pin "8") (pinfunction "NC/TDI_8") (pintype "bidirectional"))
    )
    (net (code "63") (name "unconnected-(J6-SWO{slash}TDO-Pad6)") (class "Default")
      (node (ref "J6") (pin "6") (pinfunction "SWO/TDO_6") (pintype "bidirectional"))
    )
    (net (code "64") (name "unconnected-(M1-IO4-Pad10)") (class "Default")
      (node (ref "M1") (pin "10") (pinfunction "IO4_10") (pintype "bidirectional"))
    )
    (net (code "65") (name "unconnected-(M1-IO5-Pad14)") (class "Default")
      (node (ref "M1") (pin "14") (pinfunction "IO5_14") (pintype "open_collector"))
    )
    (net (code "66") (name "unconnected-(M1-IO12-Pad4)") (class "Default")
      (node (ref "M1") (pin "4") (pinfunction "IO12_4") (pintype "bidirectional"))
    )
    (net (code "67") (name "unconnected-(M1-IO13-Pad5)") (class "Default")
      (node (ref "M1") (pin "5") (pinfunction "IO13_5") (pintype "bidirectional"))
    )
    (net (code "68") (name "unconnected-(M1-IO14-Pad3)") (class "Default")
      (node (ref "M1") (pin "3") (pinfunction "IO14_3") (pintype "bidirectional"))
    )
    (net (code "69") (name "unconnected-(M1-IO16-Pad17)") (class "Default")
      (node (ref "M1") (pin "17") (pinfunction "IO16_17") (pintype "bidirectional"))
    )
    (net (code "70") (name "unconnected-(M1-TOUT-Pad16)") (class "Default")
      (node (ref "M1") (pin "16") (pinfunction "TOUT_16") (pintype "bidirectional"))
    )
    (net (code "71") (name "unconnected-(U3-NC-Pad4)") (class "Default")
      (node (ref "U3") (pin "4") (pinfunction "NC_4") (pintype "input"))
    )
    (net (code "72") (name "~{RESET}") (class "Default")
      (node (ref "J5") (pin "12") (pinfunction "12_12") (pintype "passive"))
      (node (ref "J6") (pin "10") (pinfunction "NRESET_10") (pintype "bidirectional"))
      (node (ref "M1") (pin "15") (pinfunction "RST_15") (pintype "bidirectional"))
      (node (ref "R1") (pin "1") (pinfunction "1_1") (pintype "passive"))
      (node (ref "R4") (pin "1") (pinfunction "1_1") (pintype "passive"))
      (node (ref "S1") (pin "3") (pinfunction "2_3") (pintype "passive"))
      (node (ref "U1") (pin "40") (pinfunction "~{RESET}_40") (pintype "bidirectional"))
    )
  )
)
